# Jack_Out.net
KiCad netlist of a schematic drawn in Altium Designer
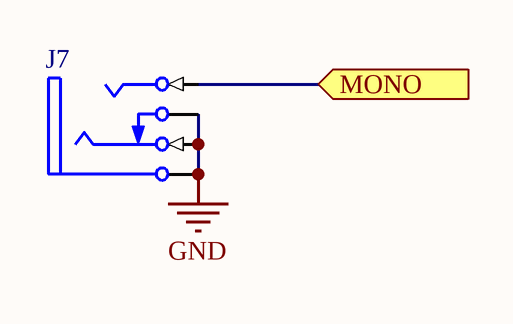
[diagram p0: Jack_Out.SchDoc]

(export (version "E")
  (design (tool "Eeschema 10.0.6"))
  (components
    (comp (ref "J7")
      (value "Phonejack3 RN")
      (footprint "MHDR1X4")
      (description "Jack Socket, 1/4\" [6.5mm], Thru-Hole, Vertical, 3-Conductor with Tip open & Ring closed")
      (fields (field (name "PUBLISHER") "Altium Limited"))
      (libsource (lib "Miscellaneous Connectors") (part "Phonejack3 RN"))
    )
  )
  (nets
    (net (code "1") (name "/MONO") (class "Default")
      (node (ref "J7") (pin "1") (pinfunction "T_1") (pintype "input"))
    )
    (net (code "2") (name "GND") (class "Default")
      (node (ref "J7") (pin "3") (pinfunction "R_3") (pintype "input"))
      (node (ref "J7") (pin "4") (pinfunction "RN_4") (pintype "passive"))
      (node (ref "J7") (pin "5") (pinfunction "S_5") (pintype "power_in"))
    )
  )
)
